# trace_7.net
KiCad netlist of a schematic drawn in Altium Designer
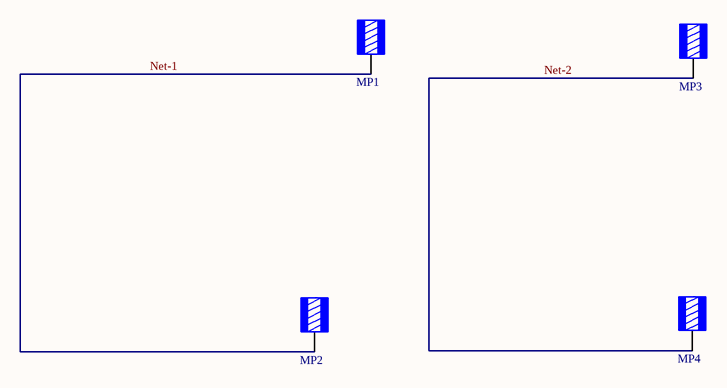
[diagram p0: trace_7.SchDoc]

(export (version "E")
  (design (tool "Eeschema 10.0.6"))
  (components
    (comp (ref "MP1")
      (value "74651194R")
      (footprint "WURTH 74651194")
      (description "TERM REDCUBE 9PIN PCB")
      (fields (field (name "MANUFACTURER") "Würth Elektronik"))
      (libsource (lib "Celestial Altium Library - altium_library") (part "MOUNTING POINT"))
    )
    (comp (ref "MP2")
      (value "74651194R")
      (footprint "WURTH 74651194")
      (description "TERM REDCUBE 9PIN PCB")
      (fields (field (name "MANUFACTURER") "Würth Elektronik"))
      (libsource (lib "Celestial Altium Library - altium_library") (part "MOUNTING POINT"))
    )
    (comp (ref "MP3")
      (value "74650073R")
      (footprint "WURTH 74650073")
      (description "TERM REDCUBE M3 4PIN PCB")
      (fields (field (name "MANUFACTURER") "Würth Elektronik"))
      (libsource (lib "Celestial Altium Library - altium_library") (part "MOUNTING POINT"))
    )
    (comp (ref "MP4")
      (value "74650073R")
      (footprint "WURTH 74650073")
      (description "TERM REDCUBE M3 4PIN PCB")
      (fields (field (name "MANUFACTURER") "Würth Elektronik"))
      (libsource (lib "Celestial Altium Library - altium_library") (part "MOUNTING POINT"))
    )
  )
  (nets
    (net (code "1") (name "/Net-1") (class "Default")
      (node (ref "MP1") (pin "1") (pinfunction "1_1") (pintype "passive"))
      (node (ref "MP2") (pin "1") (pinfunction "1_1") (pintype "passive"))
    )
    (net (code "2") (name "/Net-2") (class "Default")
      (node (ref "MP3") (pin "1") (pinfunction "1_1") (pintype "passive"))
      (node (ref "MP4") (pin "1") (pinfunction "1_1") (pintype "passive"))
    )
  )
)
